# CM_FPGA_JTAG_POWER_FLASH.net
KiCad netlist of a schematic drawn in Altium Designer
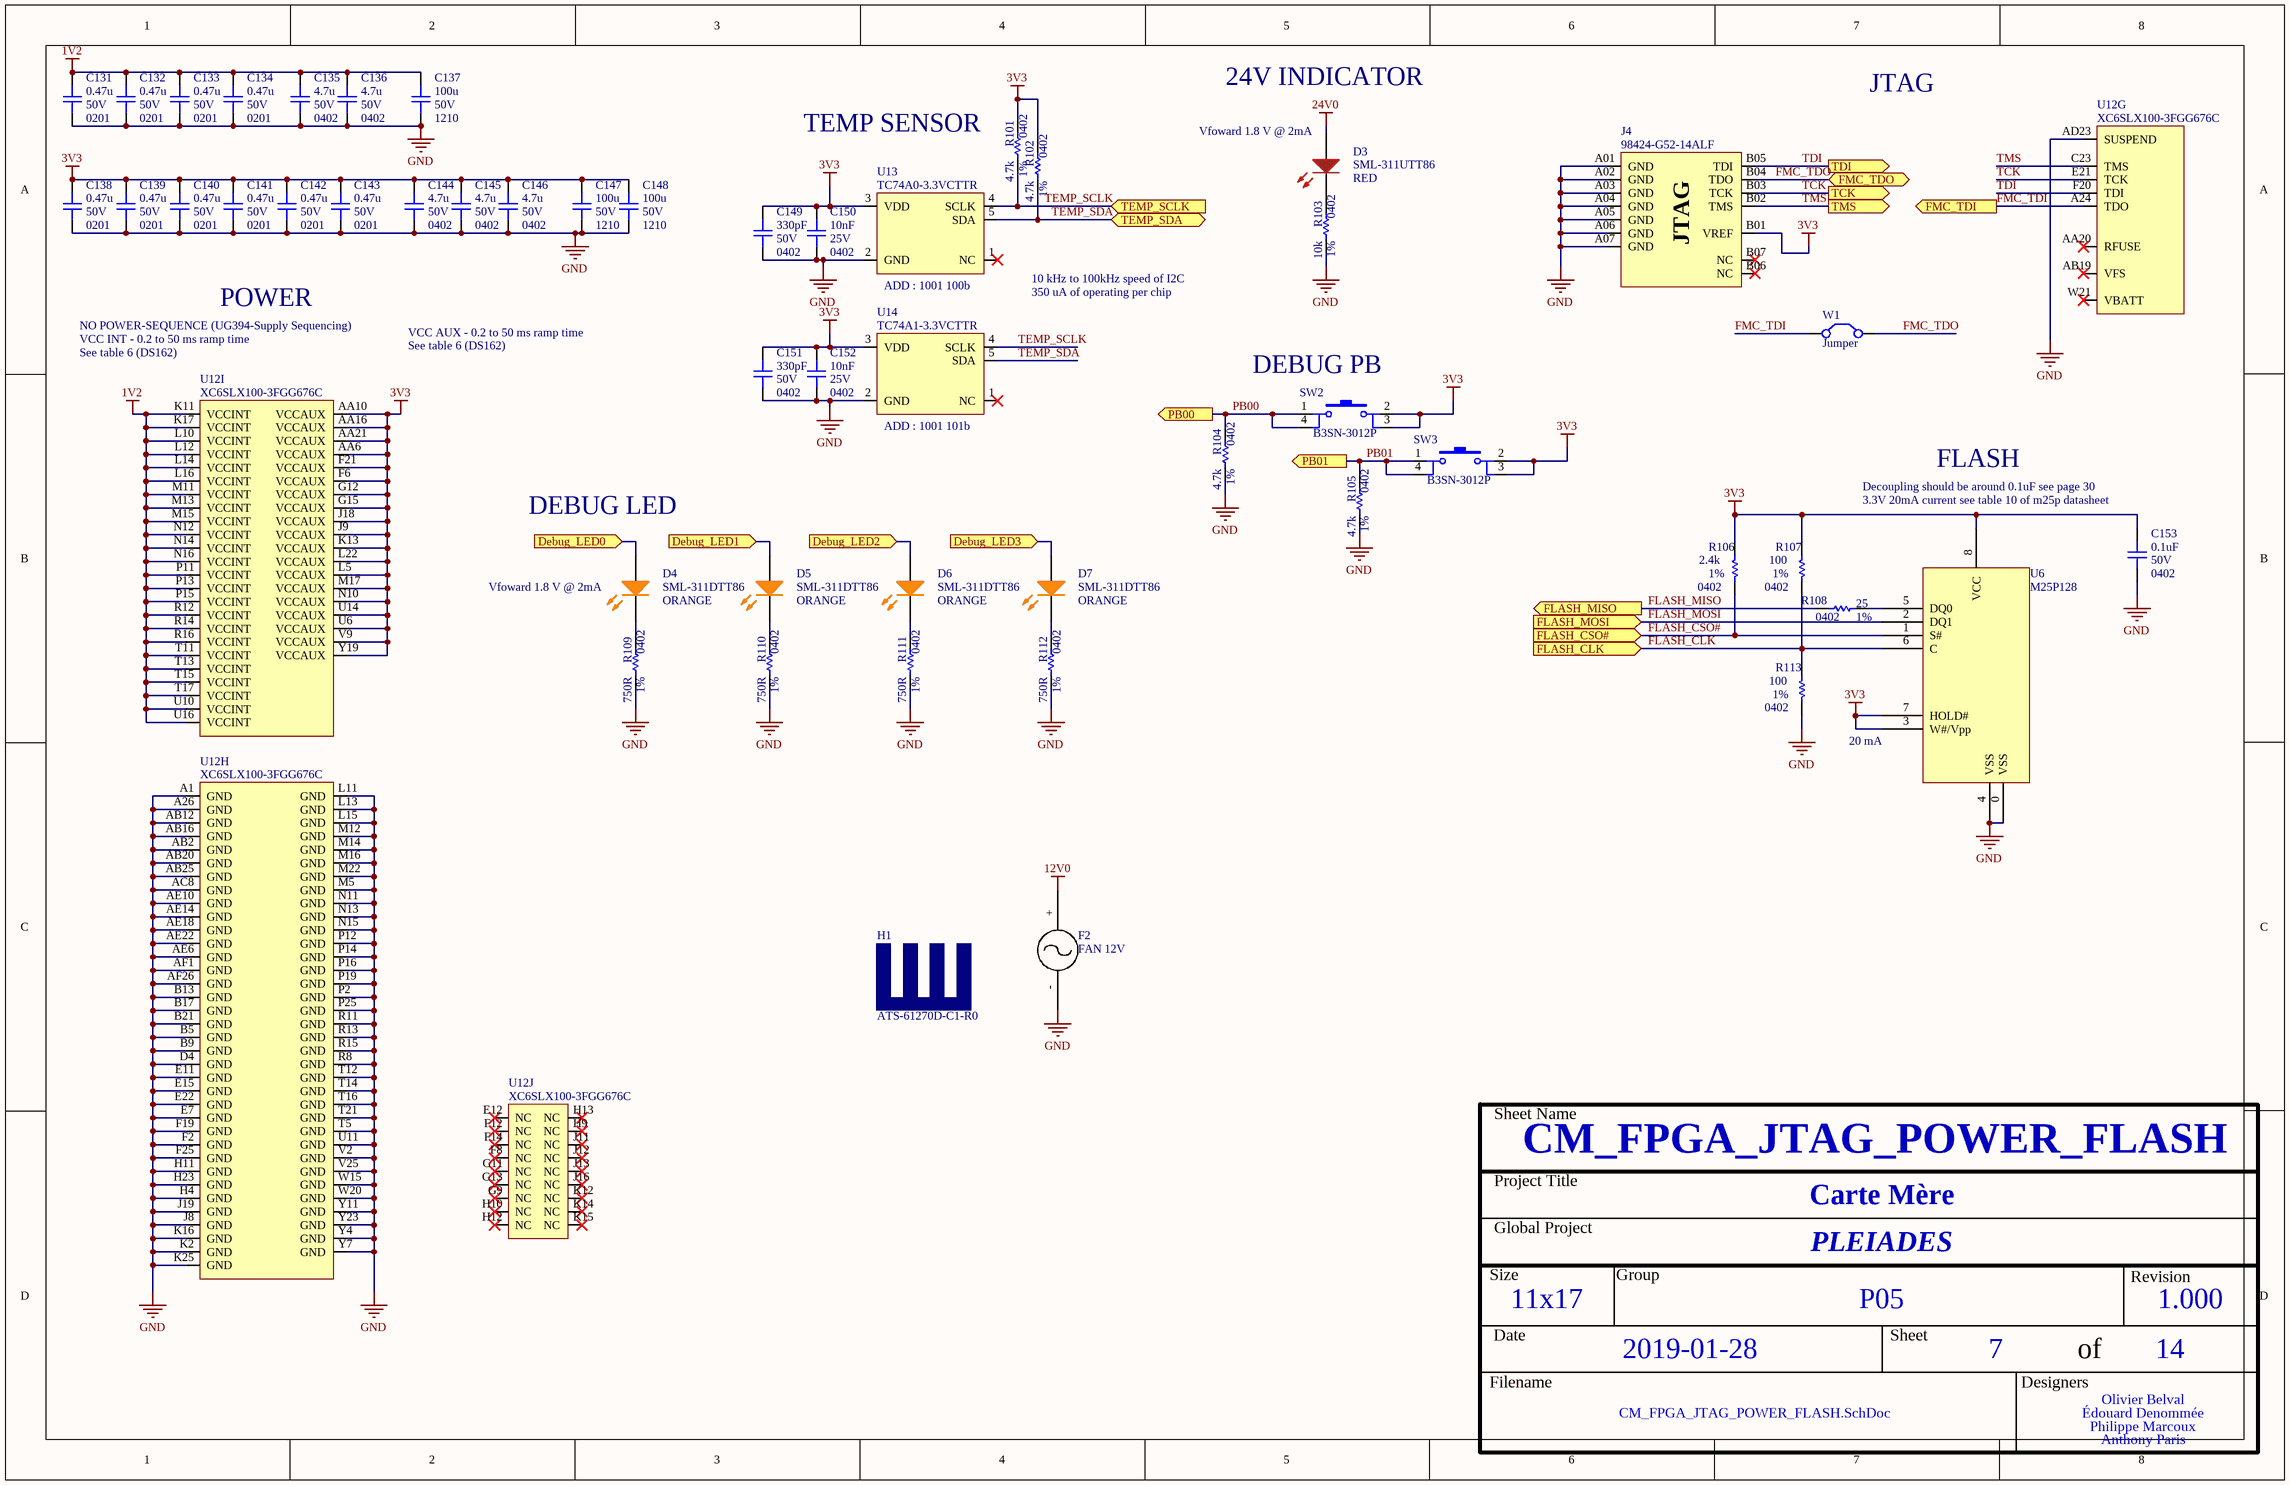
[diagram p0: CM_FPGA_JTAG_POWER_FLASH.SchDoc]

(export (version "E")
  (design (tool "Eeschema 10.0.6"))
  (components
    (comp (ref "C131")
      (value "0.47u")
      (footprint "CAP_0201")
      (description "CAP - 0201")
      (fields
        (field (name "VOLTAGE") "50V")
        (field (name "PACKAGE") "0201")
        (field (name "CREATEDBY") "Jonathan Bouchard")
      )
      (libsource (lib "S7CAS_Lib2019_REV1_00") (part "CAP - 0201"))
    )
    (comp (ref "C132")
      (value "0.47u")
      (footprint "CAP_0201")
      (description "CAP - 0201")
      (fields
        (field (name "VOLTAGE") "50V")
        (field (name "PACKAGE") "0201")
        (field (name "CREATEDBY") "Jonathan Bouchard")
      )
      (libsource (lib "S7CAS_Lib2019_REV1_00") (part "CAP - 0201"))
    )
    (comp (ref "C133")
      (value "0.47u")
      (footprint "CAP_0201")
      (description "CAP - 0201")
      (fields
        (field (name "VOLTAGE") "50V")
        (field (name "PACKAGE") "0201")
        (field (name "CREATEDBY") "Jonathan Bouchard")
      )
      (libsource (lib "S7CAS_Lib2019_REV1_00") (part "CAP - 0201"))
    )
    (comp (ref "C134")
      (value "0.47u")
      (footprint "CAP_0201")
      (description "CAP - 0201")
      (fields
        (field (name "VOLTAGE") "50V")
        (field (name "PACKAGE") "0201")
        (field (name "CREATEDBY") "Jonathan Bouchard")
      )
      (libsource (lib "S7CAS_Lib2019_REV1_00") (part "CAP - 0201"))
    )
    (comp (ref "C135")
      (value "4.7u")
      (footprint "CAP_0402")
      (description "CAP - 0402")
      (fields
        (field (name "VOLTAGE") "50V")
        (field (name "PACKAGE") "0402")
        (field (name "CREATEDBY") "Jonathan Bouchard")
      )
      (libsource (lib "S7CAS_Lib2019_REV1_00") (part "CAP - 0402"))
    )
    (comp (ref "C136")
      (value "4.7u")
      (footprint "CAP_0402")
      (description "CAP - 0402")
      (fields
        (field (name "VOLTAGE") "50V")
        (field (name "PACKAGE") "0402")
        (field (name "CREATEDBY") "Jonathan Bouchard")
      )
      (libsource (lib "S7CAS_Lib2019_REV1_00") (part "CAP - 0402"))
    )
    (comp (ref "C137")
      (value "100u")
      (footprint "CAP_1210")
      (description "CAP - 1210")
      (fields
        (field (name "VOLTAGE") "50V")
        (field (name "PACKAGE") "1210")
        (field (name "CREATEDBY") "Jonathan Bouchard")
      )
      (libsource (lib "S7CAS_Lib2019_REV1_00") (part "CAP - 1210"))
    )
    (comp (ref "C138")
      (value "0.47u")
      (footprint "CAP_0201")
      (description "CAP - 0201")
      (fields
        (field (name "VOLTAGE") "50V")
        (field (name "PACKAGE") "0201")
        (field (name "CREATEDBY") "Jonathan Bouchard")
      )
      (libsource (lib "S7CAS_Lib2019_REV1_00") (part "CAP - 0201"))
    )
    (comp (ref "C139")
      (value "0.47u")
      (footprint "CAP_0201")
      (description "CAP - 0201")
      (fields
        (field (name "VOLTAGE") "50V")
        (field (name "PACKAGE") "0201")
        (field (name "CREATEDBY") "Jonathan Bouchard")
      )
      (libsource (lib "S7CAS_Lib2019_REV1_00") (part "CAP - 0201"))
    )
    (comp (ref "C140")
      (value "0.47u")
      (footprint "CAP_0201")
      (description "CAP - 0201")
      (fields
        (field (name "VOLTAGE") "50V")
        (field (name "PACKAGE") "0201")
        (field (name "CREATEDBY") "Jonathan Bouchard")
      )
      (libsource (lib "S7CAS_Lib2019_REV1_00") (part "CAP - 0201"))
    )
    (comp (ref "C141")
      (value "0.47u")
      (footprint "CAP_0201")
      (description "CAP - 0201")
      (fields
        (field (name "VOLTAGE") "50V")
        (field (name "PACKAGE") "0201")
        (field (name "CREATEDBY") "Jonathan Bouchard")
      )
      (libsource (lib "S7CAS_Lib2019_REV1_00") (part "CAP - 0201"))
    )
    (comp (ref "C142")
      (value "0.47u")
      (footprint "CAP_0201")
      (description "CAP - 0201")
      (fields
        (field (name "VOLTAGE") "50V")
        (field (name "PACKAGE") "0201")
        (field (name "CREATEDBY") "Jonathan Bouchard")
      )
      (libsource (lib "S7CAS_Lib2019_REV1_00") (part "CAP - 0201"))
    )
    (comp (ref "C143")
      (value "0.47u")
      (footprint "CAP_0201")
      (description "CAP - 0201")
      (fields
        (field (name "VOLTAGE") "50V")
        (field (name "PACKAGE") "0201")
        (field (name "CREATEDBY") "Jonathan Bouchard")
      )
      (libsource (lib "S7CAS_Lib2019_REV1_00") (part "CAP - 0201"))
    )
    (comp (ref "C144")
      (value "4.7u")
      (footprint "CAP_0402")
      (description "CAP - 0402")
      (fields
        (field (name "VOLTAGE") "50V")
        (field (name "PACKAGE") "0402")
        (field (name "CREATEDBY") "Jonathan Bouchard")
      )
      (libsource (lib "S7CAS_Lib2019_REV1_00") (part "CAP - 0402"))
    )
    (comp (ref "C145")
      (value "4.7u")
      (footprint "CAP_0402")
      (description "CAP - 0402")
      (fields
        (field (name "VOLTAGE") "50V")
        (field (name "PACKAGE") "0402")
        (field (name "CREATEDBY") "Jonathan Bouchard")
      )
      (libsource (lib "S7CAS_Lib2019_REV1_00") (part "CAP - 0402"))
    )
    (comp (ref "C146")
      (value "4.7u")
      (footprint "CAP_0402")
      (description "CAP - 0402")
      (fields
        (field (name "VOLTAGE") "50V")
        (field (name "PACKAGE") "0402")
        (field (name "CREATEDBY") "Jonathan Bouchard")
      )
      (libsource (lib "S7CAS_Lib2019_REV1_00") (part "CAP - 0402"))
    )
    (comp (ref "C147")
      (value "100u")
      (footprint "CAP_1210")
      (description "CAP - 1210")
      (fields
        (field (name "VOLTAGE") "50V")
        (field (name "PACKAGE") "1210")
        (field (name "CREATEDBY") "Jonathan Bouchard")
      )
      (libsource (lib "S7CAS_Lib2019_REV1_00") (part "CAP - 1210"))
    )
    (comp (ref "C148")
      (value "100u")
      (footprint "CAP_1210")
      (description "CAP - 1210")
      (fields
        (field (name "VOLTAGE") "50V")
        (field (name "PACKAGE") "1210")
        (field (name "CREATEDBY") "Jonathan Bouchard")
      )
      (libsource (lib "S7CAS_Lib2019_REV1_00") (part "CAP - 1210"))
    )
    (comp (ref "C149")
      (value "330pF")
      (footprint "CAP_0402")
      (description "CAP - 0402")
      (fields
        (field (name "VOLTAGE") "50V")
        (field (name "PACKAGE") "0402")
        (field (name "CREATEDBY") "Jonathan Bouchard")
      )
      (libsource (lib "S7CAS_Lib2019_REV1_00") (part "CAP - 0402"))
    )
    (comp (ref "C150")
      (value "10nF")
      (footprint "CAP_0402")
      (description "CAP - 0402")
      (fields
        (field (name "VOLTAGE") "25V")
        (field (name "PACKAGE") "0402")
        (field (name "CREATEDBY") "Jonathan Bouchard")
      )
      (libsource (lib "S7CAS_Lib2019_REV1_00") (part "CAP - 0402"))
    )
    (comp (ref "C151")
      (value "330pF")
      (footprint "CAP_0402")
      (description "CAP - 0402")
      (fields
        (field (name "VOLTAGE") "50V")
        (field (name "PACKAGE") "0402")
        (field (name "CREATEDBY") "Jonathan Bouchard")
      )
      (libsource (lib "S7CAS_Lib2019_REV1_00") (part "CAP - 0402"))
    )
    (comp (ref "C152")
      (value "10nF")
      (footprint "CAP_0402")
      (description "CAP - 0402")
      (fields
        (field (name "VOLTAGE") "25V")
        (field (name "PACKAGE") "0402")
        (field (name "CREATEDBY") "Jonathan Bouchard")
      )
      (libsource (lib "S7CAS_Lib2019_REV1_00") (part "CAP - 0402"))
    )
    (comp (ref "C153")
      (value "0.1uF")
      (footprint "CAP_0402")
      (description "CAP - 0402")
      (fields
        (field (name "VOLTAGE") "50V")
        (field (name "PACKAGE") "0402")
        (field (name "CREATEDBY") "Jonathan Bouchard")
      )
      (libsource (lib "S7CAS_Lib2019_REV1_00") (part "CAP - 0402"))
    )
    (comp (ref "D3")
      (value "SML-311UTT86")
      (footprint "LED_0603")
      (description "LED - 620nM RED 2mA - 0603")
      (fields
        (field (name "VOLTAGE") "1.8V")
        (field (name "MFG") "ROHM Semiconductor")
        (field (name "ALTIUM_VALUE") "RED")
        (field (name "CREATEDBY") "Jonathan Bouchard")
      )
      (libsource (lib "S7CAS_Lib2019_REV1_00") (part "LED_SML-311UTT86"))
    )
    (comp (ref "D4")
      (value "SML-311DTT86")
      (footprint "LED_0603")
      (description "LED - 611nM ORANGE 2mA - 0603")
      (fields
        (field (name "VOLTAGE") "1.8V")
        (field (name "MFG") "ROHM Semiconductor")
        (field (name "ALTIUM_VALUE") "ORANGE")
        (field (name "CREATEDBY") "Jonathan Bouchard")
      )
      (libsource (lib "S7CAS_Lib2019_REV1_00") (part "LED_SML-311DTT86"))
    )
    (comp (ref "D5")
      (value "SML-311DTT86")
      (footprint "LED_0603")
      (description "LED - 611nM ORANGE 2mA - 0603")
      (fields
        (field (name "VOLTAGE") "1.8V")
        (field (name "MFG") "ROHM Semiconductor")
        (field (name "ALTIUM_VALUE") "ORANGE")
        (field (name "CREATEDBY") "Jonathan Bouchard")
      )
      (libsource (lib "S7CAS_Lib2019_REV1_00") (part "LED_SML-311DTT86"))
    )
    (comp (ref "D6")
      (value "SML-311DTT86")
      (footprint "LED_0603")
      (description "LED - 611nM ORANGE 2mA - 0603")
      (fields
        (field (name "VOLTAGE") "1.8V")
        (field (name "MFG") "ROHM Semiconductor")
        (field (name "ALTIUM_VALUE") "ORANGE")
        (field (name "CREATEDBY") "Jonathan Bouchard")
      )
      (libsource (lib "S7CAS_Lib2019_REV1_00") (part "LED_SML-311DTT86"))
    )
    (comp (ref "D7")
      (value "SML-311DTT86")
      (footprint "LED_0603")
      (description "LED - 611nM ORANGE 2mA - 0603")
      (fields
        (field (name "VOLTAGE") "1.8V")
        (field (name "MFG") "ROHM Semiconductor")
        (field (name "ALTIUM_VALUE") "ORANGE")
        (field (name "CREATEDBY") "Jonathan Bouchard")
      )
      (libsource (lib "S7CAS_Lib2019_REV1_00") (part "LED_SML-311DTT86"))
    )
    (comp (ref "F2") (value "FAN 12V") (footprint "HDR1X2") (libsource (lib "Custom") (part "FAN 12V")))
    (comp (ref "H1")
      (value "ATS-61270D-C1-R0")
      (footprint "27mm heatsink")
      (description "27mm Heatsink")
      (libsource (lib "Custom") (part "ATS-61270D-C1-R0"))
    )
    (comp (ref "J4")
      (value "98424-G52-14ALF")
      (footprint "CON_JTAG_98424-G52-14ALF")
      (description "CONN -  JTAG HEADER XILINX - 14-SMD")
      (fields (field (name "MFG") "Amphenol") (field (name "CREATEDBY") "Jonathan Bouchard"))
      (libsource (lib "S7CAS_Lib2019_REV1_00") (part "CONN_JTAG_98424-G52-14ALF"))
    )
    (comp (ref "R101")
      (value "4.7k")
      (footprint "RES_0402")
      (description "RES - 0402")
      (fields
        (field (name "VOLTAGE") "50V")
        (field (name "POWER") "1/16W")
        (field (name "PACKAGE") "0402")
        (field (name "PRECISION") "1%")
        (field (name "CREATEDBY") "Jonathan Bouchard")
      )
      (libsource (lib "S7CAS_Lib2019_REV1_00") (part "RES - 0402"))
    )
    (comp (ref "R102")
      (value "4.7k")
      (footprint "RES_0402")
      (description "RES - 0402")
      (fields
        (field (name "VOLTAGE") "50V")
        (field (name "POWER") "1/16W")
        (field (name "PACKAGE") "0402")
        (field (name "PRECISION") "1%")
        (field (name "CREATEDBY") "Jonathan Bouchard")
      )
      (libsource (lib "S7CAS_Lib2019_REV1_00") (part "RES - 0402"))
    )
    (comp (ref "R103")
      (value "10k")
      (footprint "RES_0402")
      (description "RES - 0402")
      (fields
        (field (name "VOLTAGE") "50V")
        (field (name "POWER") "1/16W")
        (field (name "PACKAGE") "0402")
        (field (name "PRECISION") "1%")
        (field (name "CREATEDBY") "Jonathan Bouchard")
      )
      (libsource (lib "S7CAS_Lib2019_REV1_00") (part "RES - 0402"))
    )
    (comp (ref "R104")
      (value "4.7k")
      (footprint "RES_0402")
      (description "RES - 0402")
      (fields
        (field (name "VOLTAGE") "50V")
        (field (name "POWER") "1/16W")
        (field (name "PACKAGE") "0402")
        (field (name "PRECISION") "1%")
        (field (name "CREATEDBY") "Jonathan Bouchard")
      )
      (libsource (lib "S7CAS_Lib2019_REV1_00") (part "RES - 0402"))
    )
    (comp (ref "R105")
      (value "4.7k")
      (footprint "RES_0402")
      (description "RES - 0402")
      (fields
        (field (name "VOLTAGE") "50V")
        (field (name "POWER") "1/16W")
        (field (name "PACKAGE") "0402")
        (field (name "PRECISION") "1%")
        (field (name "CREATEDBY") "Jonathan Bouchard")
      )
      (libsource (lib "S7CAS_Lib2019_REV1_00") (part "RES - 0402"))
    )
    (comp (ref "R106")
      (value "2.4k")
      (footprint "RES_0402")
      (description "RES - 0402")
      (fields
        (field (name "VOLTAGE") "50V")
        (field (name "POWER") "1/16W")
        (field (name "PACKAGE") "0402")
        (field (name "PRECISION") "1%")
        (field (name "CREATEDBY") "Jonathan Bouchard")
      )
      (libsource (lib "S7CAS_Lib2019_REV1_00") (part "RES - 0402"))
    )
    (comp (ref "R107")
      (value "100")
      (footprint "RES_0402")
      (description "RES - 0402")
      (fields
        (field (name "VOLTAGE") "50V")
        (field (name "POWER") "1/16W")
        (field (name "PACKAGE") "0402")
        (field (name "PRECISION") "1%")
        (field (name "CREATEDBY") "Jonathan Bouchard")
      )
      (libsource (lib "S7CAS_Lib2019_REV1_00") (part "RES - 0402"))
    )
    (comp (ref "R108")
      (value "25")
      (footprint "RES_0402")
      (description "RES - 0402")
      (fields
        (field (name "VOLTAGE") "50V")
        (field (name "POWER") "1/16W")
        (field (name "PACKAGE") "0402")
        (field (name "PRECISION") "1%")
        (field (name "CREATEDBY") "Jonathan Bouchard")
      )
      (libsource (lib "S7CAS_Lib2019_REV1_00") (part "RES - 0402"))
    )
    (comp (ref "R109")
      (value "750R")
      (footprint "RES_0402")
      (description "RES - 0402")
      (fields
        (field (name "VOLTAGE") "50V")
        (field (name "POWER") "1/16W")
        (field (name "PACKAGE") "0402")
        (field (name "PRECISION") "1%")
        (field (name "CREATEDBY") "Jonathan Bouchard")
      )
      (libsource (lib "S7CAS_Lib2019_REV1_00") (part "RES - 0402"))
    )
    (comp (ref "R110")
      (value "750R")
      (footprint "RES_0402")
      (description "RES - 0402")
      (fields
        (field (name "VOLTAGE") "50V")
        (field (name "POWER") "1/16W")
        (field (name "PACKAGE") "0402")
        (field (name "PRECISION") "1%")
        (field (name "CREATEDBY") "Jonathan Bouchard")
      )
      (libsource (lib "S7CAS_Lib2019_REV1_00") (part "RES - 0402"))
    )
    (comp (ref "R111")
      (value "750R")
      (footprint "RES_0402")
      (description "RES - 0402")
      (fields
        (field (name "VOLTAGE") "50V")
        (field (name "POWER") "1/16W")
        (field (name "PACKAGE") "0402")
        (field (name "PRECISION") "1%")
        (field (name "CREATEDBY") "Jonathan Bouchard")
      )
      (libsource (lib "S7CAS_Lib2019_REV1_00") (part "RES - 0402"))
    )
    (comp (ref "R112")
      (value "750R")
      (footprint "RES_0402")
      (description "RES - 0402")
      (fields
        (field (name "VOLTAGE") "50V")
        (field (name "POWER") "1/16W")
        (field (name "PACKAGE") "0402")
        (field (name "PRECISION") "1%")
        (field (name "CREATEDBY") "Jonathan Bouchard")
      )
      (libsource (lib "S7CAS_Lib2019_REV1_00") (part "RES - 0402"))
    )
    (comp (ref "R113")
      (value "100")
      (footprint "RES_0402")
      (description "RES - 0402")
      (fields
        (field (name "VOLTAGE") "50V")
        (field (name "POWER") "1/16W")
        (field (name "PACKAGE") "0402")
        (field (name "PRECISION") "1%")
        (field (name "CREATEDBY") "Jonathan Bouchard")
      )
      (libsource (lib "S7CAS_Lib2019_REV1_00") (part "RES - 0402"))
    )
    (comp (ref "SW2")
      (value "B3SN-3012P")
      (footprint "SWI_TACT_B3SN-3012P")
      (description "SWI - TACT SPST-NO 0.05A 24V - 4-SMD")
      (fields
        (field (name "MFG") "Omron")
        (field (name "VOLTAGE") "24V")
        (field (name "CREATEDBY") "Jonathan Bouchard")
      )
      (libsource (lib "S7CAS_Lib2019_REV1_00") (part "SWI_TACT_B3SN-3012P"))
    )
    (comp (ref "SW3")
      (value "B3SN-3012P")
      (footprint "SWI_TACT_B3SN-3012P")
      (description "SWI - TACT SPST-NO 0.05A 24V - 4-SMD")
      (fields
        (field (name "MFG") "Omron")
        (field (name "VOLTAGE") "24V")
        (field (name "CREATEDBY") "Jonathan Bouchard")
      )
      (libsource (lib "S7CAS_Lib2019_REV1_00") (part "SWI_TACT_B3SN-3012P"))
    )
    (comp (ref "U6") (value "M25P128") (footprint "M25P128") (libsource (lib "M25P128") (part "M25P128")))
    (comp (ref "U12")
      (value "XC6SLX100-3FGG676C")
      (footprint "FPGA_XILINX_FGG676")
      (description "FPGA - XILINX SPARTAN 6 480 I/O - BGA-676")
      (fields
        (field (name "VOLTAGE") "1.14 V ~ 1.26 V")
        (field (name "MFG") "Xilinx")
        (field (name "CREATEDBY") "Jonathan Bouchard")
      )
      (libsource (lib "S7CAS_Lib2019_REV1_00") (part "FPGA_XC6SLX100-3FGG676C"))
    )
    (comp (ref "U13")
      (value "TC74A0-3.3VCTTR")
      (footprint "SEN_TEMP_TC74A0-3.3VCTTR")
      (description "SENS - TEMPERATURE SENSOR I2C/SMBUS - SOT23-5")
      (fields
        (field (name "VOLTAGE") "2.7 V ~ 5.5 V")
        (field (name "MFG") "Microchip")
        (field (name "CREATEDBY") "Jonathan Bouchard")
      )
      (libsource (lib "S7CAS_Lib2019_REV1_00") (part "SENS_TEMP_TC74A0-3.3VCTTR"))
    )
    (comp (ref "U14")
      (value "TC74A1-3.3VCTTR")
      (footprint "SEN_TEMP_TC74A0-3.3VCTTR")
      (description "SENS - TEMPERATURE SENSOR I2C/SMBUS - SOT23-5")
      (fields
        (field (name "VOLTAGE") "2.7 V ~ 5.5 V")
        (field (name "MFG") "Microchip")
        (field (name "CREATEDBY") "Jonathan Bouchard")
      )
      (libsource (lib "S7CAS_Lib2019_REV1_00") (part "SENS_TEMP_TC74A0-3.3VCTTR"))
    )
    (comp (ref "W1")
      (value "Jumper")
      (footprint "RAD-0.2")
      (description "Jumper Wire")
      (fields (field (name "PUBLISHER") "Altium Limited"))
      (libsource (lib "Miscellaneous Devices") (part "Jumper"))
    )
  )
  (nets
    (net (code "1") (name "/Debug_LED0") (class "Default")
      (node (ref "D4") (pin "A") (pinfunction "A_A") (pintype "passive"))
    )
    (net (code "2") (name "/Debug_LED1") (class "Default")
      (node (ref "D5") (pin "A") (pinfunction "A_A") (pintype "passive"))
    )
    (net (code "3") (name "/Debug_LED2") (class "Default")
      (node (ref "D6") (pin "A") (pinfunction "A_A") (pintype "passive"))
    )
    (net (code "4") (name "/Debug_LED3") (class "Default")
      (node (ref "D7") (pin "A") (pinfunction "A_A") (pintype "passive"))
    )
    (net (code "5") (name "/FLASH_CLK") (class "Default")
      (node (ref "R107") (pin "1") (pinfunction "1_1") (pintype "passive"))
      (node (ref "R113") (pin "2") (pinfunction "2_2") (pintype "passive"))
      (node (ref "U6") (pin "6") (pinfunction "C_6") (pintype "passive"))
    )
    (net (code "6") (name "/FLASH_CSO#") (class "Default")
      (node (ref "R106") (pin "1") (pinfunction "1_1") (pintype "passive"))
      (node (ref "U6") (pin "1") (pinfunction "S#_1") (pintype "passive"))
    )
    (net (code "7") (name "/FLASH_MISO") (class "Default")
      (node (ref "R108") (pin "1") (pinfunction "1_1") (pintype "passive"))
    )
    (net (code "8") (name "/FLASH_MOSI") (class "Default")
      (node (ref "U6") (pin "2") (pinfunction "DQ1_2") (pintype "passive"))
    )
    (net (code "9") (name "/FMC_TDI") (class "Default")
      (node (ref "U12") (pin "A24") (pinfunction "TDO_A24") (pintype "passive"))
      (node (ref "W1") (pin "1") (pinfunction "C1_1") (pintype "passive"))
    )
    (net (code "10") (name "/FMC_TDO") (class "Default")
      (node (ref "J4") (pin "B04") (pinfunction "TDO_B04") (pintype "passive"))
      (node (ref "W1") (pin "2") (pinfunction "C2_2") (pintype "passive"))
    )
    (net (code "11") (name "/PB00") (class "Default")
      (node (ref "R104") (pin "2") (pinfunction "2_2") (pintype "passive"))
      (node (ref "SW2") (pin "1") (pinfunction "1_1") (pintype "passive"))
      (node (ref "SW2") (pin "4") (pinfunction "4_4") (pintype "passive"))
    )
    (net (code "12") (name "/PB01") (class "Default")
      (node (ref "R105") (pin "2") (pinfunction "2_2") (pintype "passive"))
      (node (ref "SW3") (pin "1") (pinfunction "1_1") (pintype "passive"))
      (node (ref "SW3") (pin "4") (pinfunction "4_4") (pintype "passive"))
    )
    (net (code "13") (name "/TCK") (class "Default")
      (node (ref "J4") (pin "B03") (pinfunction "TCK_B03") (pintype "passive"))
      (node (ref "U12") (pin "E21") (pinfunction "TCK_E21") (pintype "passive"))
    )
    (net (code "14") (name "/TDI") (class "Default")
      (node (ref "J4") (pin "B05") (pinfunction "TDI_B05") (pintype "passive"))
      (node (ref "U12") (pin "F20") (pinfunction "TDI_F20") (pintype "passive"))
    )
    (net (code "15") (name "/TEMP_SCLK") (class "Default")
      (node (ref "R101") (pin "1") (pinfunction "1_1") (pintype "passive"))
      (node (ref "U13") (pin "4") (pinfunction "SCLK_4") (pintype "passive"))
      (node (ref "U14") (pin "4") (pinfunction "SCLK_4") (pintype "passive"))
    )
    (net (code "16") (name "/TEMP_SDA") (class "Default")
      (node (ref "R102") (pin "1") (pinfunction "1_1") (pintype "passive"))
      (node (ref "U13") (pin "5") (pinfunction "SDA_5") (pintype "passive"))
      (node (ref "U14") (pin "5") (pinfunction "SDA_5") (pintype "passive"))
    )
    (net (code "17") (name "/TMS") (class "Default")
      (node (ref "J4") (pin "B02") (pinfunction "TMS_B02") (pintype "passive"))
      (node (ref "U12") (pin "C23") (pinfunction "TMS_C23") (pintype "passive"))
    )
    (net (code "18") (name "1V2") (class "Default")
      (node (ref "C131") (pin "2") (pinfunction "2_2") (pintype "passive"))
      (node (ref "C132") (pin "2") (pinfunction "2_2") (pintype "passive"))
      (node (ref "C133") (pin "2") (pinfunction "2_2") (pintype "passive"))
      (node (ref "C134") (pin "2") (pinfunction "2_2") (pintype "passive"))
      (node (ref "C135") (pin "2") (pinfunction "2_2") (pintype "passive"))
      (node (ref "C136") (pin "2") (pinfunction "2_2") (pintype "passive"))
      (node (ref "C137") (pin "2") (pinfunction "2_2") (pintype "passive"))
      (node (ref "U12") (pin "K11") (pinfunction "VCCINT_K11") (pintype "passive"))
      (node (ref "U12") (pin "K17") (pinfunction "VCCINT_K17") (pintype "passive"))
      (node (ref "U12") (pin "L10") (pinfunction "VCCINT_L10") (pintype "passive"))
      (node (ref "U12") (pin "L12") (pinfunction "VCCINT_L12") (pintype "passive"))
      (node (ref "U12") (pin "L14") (pinfunction "VCCINT_L14") (pintype "passive"))
      (node (ref "U12") (pin "L16") (pinfunction "VCCINT_L16") (pintype "passive"))
      (node (ref "U12") (pin "M11") (pinfunction "VCCINT_M11") (pintype "passive"))
      (node (ref "U12") (pin "M13") (pinfunction "VCCINT_M13") (pintype "passive"))
      (node (ref "U12") (pin "M15") (pinfunction "VCCINT_M15") (pintype "passive"))
      (node (ref "U12") (pin "N12") (pinfunction "VCCINT_N12") (pintype "passive"))
      (node (ref "U12") (pin "N14") (pinfunction "VCCINT_N14") (pintype "passive"))
      (node (ref "U12") (pin "N16") (pinfunction "VCCINT_N16") (pintype "passive"))
      (node (ref "U12") (pin "P11") (pinfunction "VCCINT_P11") (pintype "passive"))
      (node (ref "U12") (pin "P13") (pinfunction "VCCINT_P13") (pintype "passive"))
      (node (ref "U12") (pin "P15") (pinfunction "VCCINT_P15") (pintype "passive"))
      (node (ref "U12") (pin "R12") (pinfunction "VCCINT_R12") (pintype "passive"))
      (node (ref "U12") (pin "R14") (pinfunction "VCCINT_R14") (pintype "passive"))
      (node (ref "U12") (pin "R16") (pinfunction "VCCINT_R16") (pintype "passive"))
      (node (ref "U12") (pin "T11") (pinfunction "VCCINT_T11") (pintype "passive"))
      (node (ref "U12") (pin "T13") (pinfunction "VCCINT_T13") (pintype "passive"))
      (node (ref "U12") (pin "T15") (pinfunction "VCCINT_T15") (pintype "passive"))
      (node (ref "U12") (pin "T17") (pinfunction "VCCINT_T17") (pintype "passive"))
      (node (ref "U12") (pin "U10") (pinfunction "VCCINT_U10") (pintype "passive"))
      (node (ref "U12") (pin "U16") (pinfunction "VCCINT_U16") (pintype "passive"))
    )
    (net (code "19") (name "3V3") (class "Default")
      (node (ref "C138") (pin "2") (pinfunction "2_2") (pintype "passive"))
      (node (ref "C139") (pin "2") (pinfunction "2_2") (pintype "passive"))
      (node (ref "C140") (pin "2") (pinfunction "2_2") (pintype "passive"))
      (node (ref "C141") (pin "2") (pinfunction "2_2") (pintype "passive"))
      (node (ref "C142") (pin "2") (pinfunction "2_2") (pintype "passive"))
      (node (ref "C143") (pin "2") (pinfunction "2_2") (pintype "passive"))
      (node (ref "C144") (pin "2") (pinfunction "2_2") (pintype "passive"))
      (node (ref "C145") (pin "2") (pinfunction "2_2") (pintype "passive"))
      (node (ref "C146") (pin "2") (pinfunction "2_2") (pintype "passive"))
      (node (ref "C147") (pin "2") (pinfunction "2_2") (pintype "passive"))
      (node (ref "C148") (pin "2") (pinfunction "2_2") (pintype "passive"))
      (node (ref "C149") (pin "2") (pinfunction "2_2") (pintype "passive"))
      (node (ref "C150") (pin "2") (pinfunction "2_2") (pintype "passive"))
      (node (ref "C151") (pin "2") (pinfunction "2_2") (pintype "passive"))
      (node (ref "C152") (pin "2") (pinfunction "2_2") (pintype "passive"))
      (node (ref "C153") (pin "2") (pinfunction "2_2") (pintype "passive"))
      (node (ref "J4") (pin "B01") (pinfunction "VREF_B01") (pintype "passive"))
      (node (ref "R101") (pin "2") (pinfunction "2_2") (pintype "passive"))
      (node (ref "R102") (pin "2") (pinfunction "2_2") (pintype "passive"))
      (node (ref "R106") (pin "2") (pinfunction "2_2") (pintype "passive"))
      (node (ref "R107") (pin "2") (pinfunction "2_2") (pintype "passive"))
      (node (ref "SW2") (pin "2") (pinfunction "2_2") (pintype "passive"))
      (node (ref "SW2") (pin "3") (pinfunction "3_3") (pintype "passive"))
      (node (ref "SW3") (pin "2") (pinfunction "2_2") (pintype "passive"))
      (node (ref "SW3") (pin "3") (pinfunction "3_3") (pintype "passive"))
      (node (ref "U12") (pin "AA10") (pinfunction "VCCAUX_AA10") (pintype "passive"))
      (node (ref "U12") (pin "AA16") (pinfunction "VCCAUX_AA16") (pintype "passive"))
      (node (ref "U12") (pin "AA21") (pinfunction "VCCAUX_AA21") (pintype "passive"))
      (node (ref "U12") (pin "AA6") (pinfunction "VCCAUX_AA6") (pintype "passive"))
      (node (ref "U12") (pin "F21") (pinfunction "VCCAUX_F21") (pintype "passive"))
      (node (ref "U12") (pin "F6") (pinfunction "VCCAUX_F6") (pintype "passive"))
      (node (ref "U12") (pin "G12") (pinfunction "VCCAUX_G12") (pintype "passive"))
      (node (ref "U12") (pin "G15") (pinfunction "VCCAUX_G15") (pintype "passive"))
      (node (ref "U12") (pin "J18") (pinfunction "VCCAUX_J18") (pintype "passive"))
      (node (ref "U12") (pin "J9") (pinfunction "VCCAUX_J9") (pintype "passive"))
      (node (ref "U12") (pin "K13") (pinfunction "VCCAUX_K13") (pintype "passive"))
      (node (ref "U12") (pin "L22") (pinfunction "VCCAUX_L22") (pintype "passive"))
      (node (ref "U12") (pin "L5") (pinfunction "VCCAUX_L5") (pintype "passive"))
      (node (ref "U12") (pin "M17") (pinfunction "VCCAUX_M17") (pintype "passive"))
      (node (ref "U12") (pin "N10") (pinfunction "VCCAUX_N10") (pintype "passive"))
      (node (ref "U12") (pin "U14") (pinfunction "VCCAUX_U14") (pintype "passive"))
      (node (ref "U12") (pin "U6") (pinfunction "VCCAUX_U6") (pintype "passive"))
      (node (ref "U12") (pin "V9") (pinfunction "VCCAUX_V9") (pintype "passive"))
      (node (ref "U12") (pin "Y19") (pinfunction "VCCAUX_Y19") (pintype "passive"))
      (node (ref "U13") (pin "3") (pinfunction "VDD_3") (pintype "passive"))
      (node (ref "U14") (pin "3") (pinfunction "VDD_3") (pintype "passive"))
      (node (ref "U6") (pin "3") (pinfunction "W#/Vpp_3") (pintype "passive"))
      (node (ref "U6") (pin "7") (pinfunction "HOLD#_7") (pintype "passive"))
      (node (ref "U6") (pin "8") (pinfunction "VCC_8") (pintype "passive"))
    )
    (net (code "20") (name "12V0") (class "Default") (node (ref "F2") (pin "+") (pintype "passive")))
    (net (code "21") (name "24V0") (class "Default")
      (node (ref "D3") (pin "A") (pinfunction "A_A") (pintype "passive"))
    )
    (net (code "22") (name "GND") (class "Default")
      (node (ref "C131") (pin "1") (pinfunction "1_1") (pintype "passive"))
      (node (ref "C132") (pin "1") (pinfunction "1_1") (pintype "passive"))
      (node (ref "C133") (pin "1") (pinfunction "1_1") (pintype "passive"))
      (node (ref "C134") (pin "1") (pinfunction "1_1") (pintype "passive"))
      (node (ref "C135") (pin "1") (pinfunction "1_1") (pintype "passive"))
      (node (ref "C136") (pin "1") (pinfunction "1_1") (pintype "passive"))
      (node (ref "C137") (pin "1") (pinfunction "1_1") (pintype "passive"))
      (node (ref "C138") (pin "1") (pinfunction "1_1") (pintype "passive"))
      (node (ref "C139") (pin "1") (pinfunction "1_1") (pintype "passive"))
      (node (ref "C140") (pin "1") (pinfunction "1_1") (pintype "passive"))
      (node (ref "C141") (pin "1") (pinfunction "1_1") (pintype "passive"))
      (node (ref "C142") (pin "1") (pinfunction "1_1") (pintype "passive"))
      (node (ref "C143") (pin "1") (pinfunction "1_1") (pintype "passive"))
      (node (ref "C144") (pin "1") (pinfunction "1_1") (pintype "passive"))
      (node (ref "C145") (pin "1") (pinfunction "1_1") (pintype "passive"))
      (node (ref "C146") (pin "1") (pinfunction "1_1") (pintype "passive"))
      (node (ref "C147") (pin "1") (pinfunction "1_1") (pintype "passive"))
      (node (ref "C148") (pin "1") (pinfunction "1_1") (pintype "passive"))
      (node (ref "C149") (pin "1") (pinfunction "1_1") (pintype "passive"))
      (node (ref "C150") (pin "1") (pinfunction "1_1") (pintype "passive"))
      (node (ref "C151") (pin "1") (pinfunction "1_1") (pintype "passive"))
      (node (ref "C152") (pin "1") (pinfunction "1_1") (pintype "passive"))
      (node (ref "C153") (pin "1") (pinfunction "1_1") (pintype "passive"))
      (node (ref "F2") (pin "-") (pintype "passive"))
      (node (ref "J4") (pin "A01") (pinfunction "GND_A01") (pintype "passive"))
      (node (ref "J4") (pin "A02") (pinfunction "GND_A02") (pintype "passive"))
      (node (ref "J4") (pin "A03") (pinfunction "GND_A03") (pintype "passive"))
      (node (ref "J4") (pin "A04") (pinfunction "GND_A04") (pintype "passive"))
      (node (ref "J4") (pin "A05") (pinfunction "GND_A05") (pintype "passive"))
      (node (ref "J4") (pin "A06") (pinfunction "GND_A06") (pintype "passive"))
      (node (ref "J4") (pin "A07") (pinfunction "GND_A07") (pintype "passive"))
      (node (ref "R103") (pin "1") (pinfunction "1_1") (pintype "passive"))
      (node (ref "R104") (pin "1") (pinfunction "1_1") (pintype "passive"))
      (node (ref "R105") (pin "1") (pinfunction "1_1") (pintype "passive"))
      (node (ref "R109") (pin "1") (pinfunction "1_1") (pintype "passive"))
      (node (ref "R110") (pin "1") (pinfunction "1_1") (pintype "passive"))
      (node (ref "R111") (pin "1") (pinfunction "1_1") (pintype "passive"))
      (node (ref "R112") (pin "1") (pinfunction "1_1") (pintype "passive"))
      (node (ref "R113") (pin "1") (pinfunction "1_1") (pintype "passive"))
      (node (ref "U12") (pin "A1") (pinfunction "GND_A1") (pintype "passive"))
      (node (ref "U12") (pin "A26") (pinfunction "GND_A26") (pintype "passive"))
      (node (ref "U12") (pin "AB12") (pinfunction "GND_AB12") (pintype "passive"))
      (node (ref "U12") (pin "AB16") (pinfunction "GND_AB16") (pintype "passive"))
      (node (ref "U12") (pin "AB2") (pinfunction "GND_AB2") (pintype "passive"))
      (node (ref "U12") (pin "AB20") (pinfunction "GND_AB20") (pintype "passive"))
      (node (ref "U12") (pin "AB25") (pinfunction "GND_AB25") (pintype "passive"))
      (node (ref "U12") (pin "AC8") (pinfunction "GND_AC8") (pintype "passive"))
      (node (ref "U12") (pin "AD23") (pinfunction "SUSPEND_AD23") (pintype "passive"))
      (node (ref "U12") (pin "AE10") (pinfunction "GND_AE10") (pintype "passive"))
      (node (ref "U12") (pin "AE14") (pinfunction "GND_AE14") (pintype "passive"))
      (node (ref "U12") (pin "AE18") (pinfunction "GND_AE18") (pintype "passive"))
      (node (ref "U12") (pin "AE22") (pinfunction "GND_AE22") (pintype "passive"))
      (node (ref "U12") (pin "AE6") (pinfunction "GND_AE6") (pintype "passive"))
      (node (ref "U12") (pin "AF1") (pinfunction "GND_AF1") (pintype "passive"))
      (node (ref "U12") (pin "AF26") (pinfunction "GND_AF26") (pintype "passive"))
      (node (ref "U12") (pin "B13") (pinfunction "GND_B13") (pintype "passive"))
      (node (ref "U12") (pin "B17") (pinfunction "GND_B17") (pintype "passive"))
      (node (ref "U12") (pin "B21") (pinfunction "GND_B21") (pintype "passive"))
      (node (ref "U12") (pin "B5") (pinfunction "GND_B5") (pintype "passive"))
      (node (ref "U12") (pin "B9") (pinfunction "GND_B9") (pintype "passive"))
      (node (ref "U12") (pin "D4") (pinfunction "GND_D4") (pintype "passive"))
      (node (ref "U12") (pin "E11") (pinfunction "GND_E11") (pintype "passive"))
      (node (ref "U12") (pin "E15") (pinfunction "GND_E15") (pintype "passive"))
      (node (ref "U12") (pin "E22") (pinfunction "GND_E22") (pintype "passive"))
      (node (ref "U12") (pin "E7") (pinfunction "GND_E7") (pintype "passive"))
      (node (ref "U12") (pin "F19") (pinfunction "GND_F19") (pintype "passive"))
      (node (ref "U12") (pin "F2") (pinfunction "GND_F2") (pintype "passive"))
      (node (ref "U12") (pin "F25") (pinfunction "GND_F25") (pintype "passive"))
      (node (ref "U12") (pin "H11") (pinfunction "GND_H11") (pintype "passive"))
      (node (ref "U12") (pin "H23") (pinfunction "GND_H23") (pintype "passive"))
      (node (ref "U12") (pin "H4") (pinfunction "GND_H4") (pintype "passive"))
      (node (ref "U12") (pin "J19") (pinfunction "GND_J19") (pintype "passive"))
      (node (ref "U12") (pin "J8") (pinfunction "GND_J8") (pintype "passive"))
      (node (ref "U12") (pin "K16") (pinfunction "GND_K16") (pintype "passive"))
      (node (ref "U12") (pin "K2") (pinfunction "GND_K2") (pintype "passive"))
      (node (ref "U12") (pin "K25") (pinfunction "GND_K25") (pintype "passive"))
      (node (ref "U12") (pin "L11") (pinfunction "GND_L11") (pintype "passive"))
      (node (ref "U12") (pin "L13") (pinfunction "GND_L13") (pintype "passive"))
      (node (ref "U12") (pin "L15") (pinfunction "GND_L15") (pintype "passive"))
      (node (ref "U12") (pin "M12") (pinfunction "GND_M12") (pintype "passive"))
      (node (ref "U12") (pin "M14") (pinfunction "GND_M14") (pintype "passive"))
      (node (ref "U12") (pin "M16") (pinfunction "GND_M16") (pintype "passive"))
      (node (ref "U12") (pin "M22") (pinfunction "GND_M22") (pintype "passive"))
      (node (ref "U12") (pin "M5") (pinfunction "GND_M5") (pintype "passive"))
      (node (ref "U12") (pin "N11") (pinfunction "GND_N11") (pintype "passive"))
      (node (ref "U12") (pin "N13") (pinfunction "GND_N13") (pintype "passive"))
      (node (ref "U12") (pin "N15") (pinfunction "GND_N15") (pintype "passive"))
      (node (ref "U12") (pin "P12") (pinfunction "GND_P12") (pintype "passive"))
      (node (ref "U12") (pin "P14") (pinfunction "GND_P14") (pintype "passive"))
      (node (ref "U12") (pin "P16") (pinfunction "GND_P16") (pintype "passive"))
      (node (ref "U12") (pin "P19") (pinfunction "GND_P19") (pintype "passive"))
      (node (ref "U12") (pin "P2") (pinfunction "GND_P2") (pintype "passive"))
      (node (ref "U12") (pin "P25") (pinfunction "GND_P25") (pintype "passive"))
      (node (ref "U12") (pin "R11") (pinfunction "GND_R11") (pintype "passive"))
      (node (ref "U12") (pin "R13") (pinfunction "GND_R13") (pintype "passive"))
      (node (ref "U12") (pin "R15") (pinfunction "GND_R15") (pintype "passive"))
      (node (ref "U12") (pin "R8") (pinfunction "GND_R8") (pintype "passive"))
      (node (ref "U12") (pin "T12") (pinfunction "GND_T12") (pintype "passive"))
      (node (ref "U12") (pin "T14") (pinfunction "GND_T14") (pintype "passive"))
      (node (ref "U12") (pin "T16") (pinfunction "GND_T16") (pintype "passive"))
      (node (ref "U12") (pin "T21") (pinfunction "GND_T21") (pintype "passive"))
      (node (ref "U12") (pin "T5") (pinfunction "GND_T5") (pintype "passive"))
      (node (ref "U12") (pin "U11") (pinfunction "GND_U11") (pintype "passive"))
      (node (ref "U12") (pin "V2") (pinfunction "GND_V2") (pintype "passive"))
      (node (ref "U12") (pin "V25") (pinfunction "GND_V25") (pintype "passive"))
      (node (ref "U12") (pin "W15") (pinfunction "GND_W15") (pintype "passive"))
      (node (ref "U12") (pin "W20") (pinfunction "GND_W20") (pintype "passive"))
      (node (ref "U12") (pin "Y11") (pinfunction "GND_Y11") (pintype "passive"))
      (node (ref "U12") (pin "Y23") (pinfunction "GND_Y23") (pintype "passive"))
      (node (ref "U12") (pin "Y4") (pinfunction "GND_Y4") (pintype "passive"))
      (node (ref "U12") (pin "Y7") (pinfunction "GND_Y7") (pintype "passive"))
      (node (ref "U13") (pin "2") (pinfunction "GND_2") (pintype "passive"))
      (node (ref "U14") (pin "2") (pinfunction "GND_2") (pintype "passive"))
      (node (ref "U6") (pin "0") (pinfunction "VSS_0") (pintype "passive"))
      (node (ref "U6") (pin "4") (pinfunction "VSS_4") (pintype "passive"))
    )
    (net (code "23") (name "Net-(D3-PadK)") (class "Default")
      (node (ref "D3") (pin "K") (pinfunction "K_K") (pintype "passive"))
      (node (ref "R103") (pin "2") (pinfunction "2_2") (pintype "passive"))
    )
    (net (code "24") (name "Net-(D4-PadK)") (class "Default")
      (node (ref "D4") (pin "K") (pinfunction "K_K") (pintype "passive"))
      (node (ref "R109") (pin "2") (pinfunction "2_2") (pintype "passive"))
    )
    (net (code "25") (name "Net-(D5-PadK)") (class "Default")
      (node (ref "D5") (pin "K") (pinfunction "K_K") (pintype "passive"))
      (node (ref "R110") (pin "2") (pinfunction "2_2") (pintype "passive"))
    )
    (net (code "26") (name "Net-(D6-PadK)") (class "Default")
      (node (ref "D6") (pin "K") (pinfunction "K_K") (pintype "passive"))
      (node (ref "R111") (pin "2") (pinfunction "2_2") (pintype "passive"))
    )
    (net (code "27") (name "Net-(D7-PadK)") (class "Default")
      (node (ref "D7") (pin "K") (pinfunction "K_K") (pintype "passive"))
      (node (ref "R112") (pin "2") (pinfunction "2_2") (pintype "passive"))
    )
    (net (code "28") (name "Net-(U6-DQ0)") (class "Default")
      (node (ref "R108") (pin "2") (pinfunction "2_2") (pintype "passive"))
      (node (ref "U6") (pin "5") (pinfunction "DQ0_5") (pintype "passive"))
    )
    (net (code "29") (name "unconnected-(J4-NC-PadB06)") (class "Default")
      (node (ref "J4") (pin "B06") (pinfunction "NC_B06") (pintype "passive+no_connect"))
    )
    (net (code "30") (name "unconnected-(J4-NC-PadB07)") (class "Default")
      (node (ref "J4") (pin "B07") (pinfunction "NC_B07") (pintype "passive+no_connect"))
    )
    (net (code "31") (name "unconnected-(U12G-RFUSE-PadAA20)") (class "Default")
      (node (ref "U12") (pin "AA20") (pinfunction "RFUSE_AA20") (pintype "passive+no_connect"))
    )
    (net (code "32") (name "unconnected-(U12G-VBATT-PadW21)") (class "Default")
      (node (ref "U12") (pin "W21") (pinfunction "VBATT_W21") (pintype "passive+no_connect"))
    )
    (net (code "33") (name "unconnected-(U12G-VFS-PadAB19)") (class "Default")
      (node (ref "U12") (pin "AB19") (pinfunction "VFS_AB19") (pintype "passive+no_connect"))
    )
    (net (code "34") (name "unconnected-(U12J-NC-PadE12)") (class "Default")
      (node (ref "U12") (pin "E12") (pinfunction "NC_E12") (pintype "passive+no_connect"))
    )
    (net (code "35") (name "unconnected-(U12J-NC-PadF8)") (class "Default")
      (node (ref "U12") (pin "F8") (pinfunction "NC_F8") (pintype "passive+no_connect"))
    )
    (net (code "36") (name "unconnected-(U12J-NC-PadF12)") (class "Default")
      (node (ref "U12") (pin "F12") (pinfunction "NC_F12") (pintype "passive+no_connect"))
    )
    (net (code "37") (name "unconnected-(U12J-NC-PadF14)") (class "Default")
      (node (ref "U12") (pin "F14") (pinfunction "NC_F14") (pintype "passive+no_connect"))
    )
    (net (code "38") (name "unconnected-(U12J-NC-PadG9)") (class "Default")
      (node (ref "U12") (pin "G9") (pinfunction "NC_G9") (pintype "passive+no_connect"))
    )
    (net (code "39") (name "unconnected-(U12J-NC-PadG11)") (class "Default")
      (node (ref "U12") (pin "G11") (pinfunction "NC_G11") (pintype "passive+no_connect"))
    )
    (net (code "40") (name "unconnected-(U12J-NC-PadG13)") (class "Default")
      (node (ref "U12") (pin "G13") (pinfunction "NC_G13") (pintype "passive+no_connect"))
    )
    (net (code "41") (name "unconnected-(U12J-NC-PadH9)") (class "Default")
      (node (ref "U12") (pin "H9") (pinfunction "NC_H9") (pintype "passive+no_connect"))
    )
    (net (code "42") (name "unconnected-(U12J-NC-PadH10)") (class "Default")
      (node (ref "U12") (pin "H10") (pinfunction "NC_H10") (pintype "passive+no_connect"))
    )
    (net (code "43") (name "unconnected-(U12J-NC-PadH12)") (class "Default")
      (node (ref "U12") (pin "H12") (pinfunction "NC_H12") (pintype "passive+no_connect"))
    )
    (net (code "44") (name "unconnected-(U12J-NC-PadH13)") (class "Default")
      (node (ref "U12") (pin "H13") (pinfunction "NC_H13") (pintype "passive+no_connect"))
    )
    (net (code "45") (name "unconnected-(U12J-NC-PadJ11)") (class "Default")
      (node (ref "U12") (pin "J11") (pinfunction "NC_J11") (pintype "passive+no_connect"))
    )
    (net (code "46") (name "unconnected-(U12J-NC-PadJ12)") (class "Default")
      (node (ref "U12") (pin "J12") (pinfunction "NC_J12") (pintype "passive+no_connect"))
    )
    (net (code "47") (name "unconnected-(U12J-NC-PadJ13)") (class "Default")
      (node (ref "U12") (pin "J13") (pinfunction "NC_J13") (pintype "passive+no_connect"))
    )
    (net (code "48") (name "unconnected-(U12J-NC-PadJ16)") (class "Default")
      (node (ref "U12") (pin "J16") (pinfunction "NC_J16") (pintype "passive+no_connect"))
    )
    (net (code "49") (name "unconnected-(U12J-NC-PadK12)") (class "Default")
      (node (ref "U12") (pin "K12") (pinfunction "NC_K12") (pintype "passive+no_connect"))
    )
    (net (code "50") (name "unconnected-(U12J-NC-PadK14)") (class "Default")
      (node (ref "U12") (pin "K14") (pinfunction "NC_K14") (pintype "passive+no_connect"))
    )
    (net (code "51") (name "unconnected-(U12J-NC-PadK15)") (class "Default")
      (node (ref "U12") (pin "K15") (pinfunction "NC_K15") (pintype "passive+no_connect"))
    )
    (net (code "52") (name "unconnected-(U13-NC-Pad1)") (class "Default")
      (node (ref "U13") (pin "1") (pinfunction "NC_1") (pintype "passive+no_connect"))
    )
    (net (code "53") (name "unconnected-(U14-NC-Pad1)") (class "Default")
      (node (ref "U14") (pin "1") (pinfunction "NC_1") (pintype "passive+no_connect"))
    )
  )
)
